# LB_BIT_o7_IRLED-v03_1_1.net
KiCad netlist of a schematic drawn in EAGLE
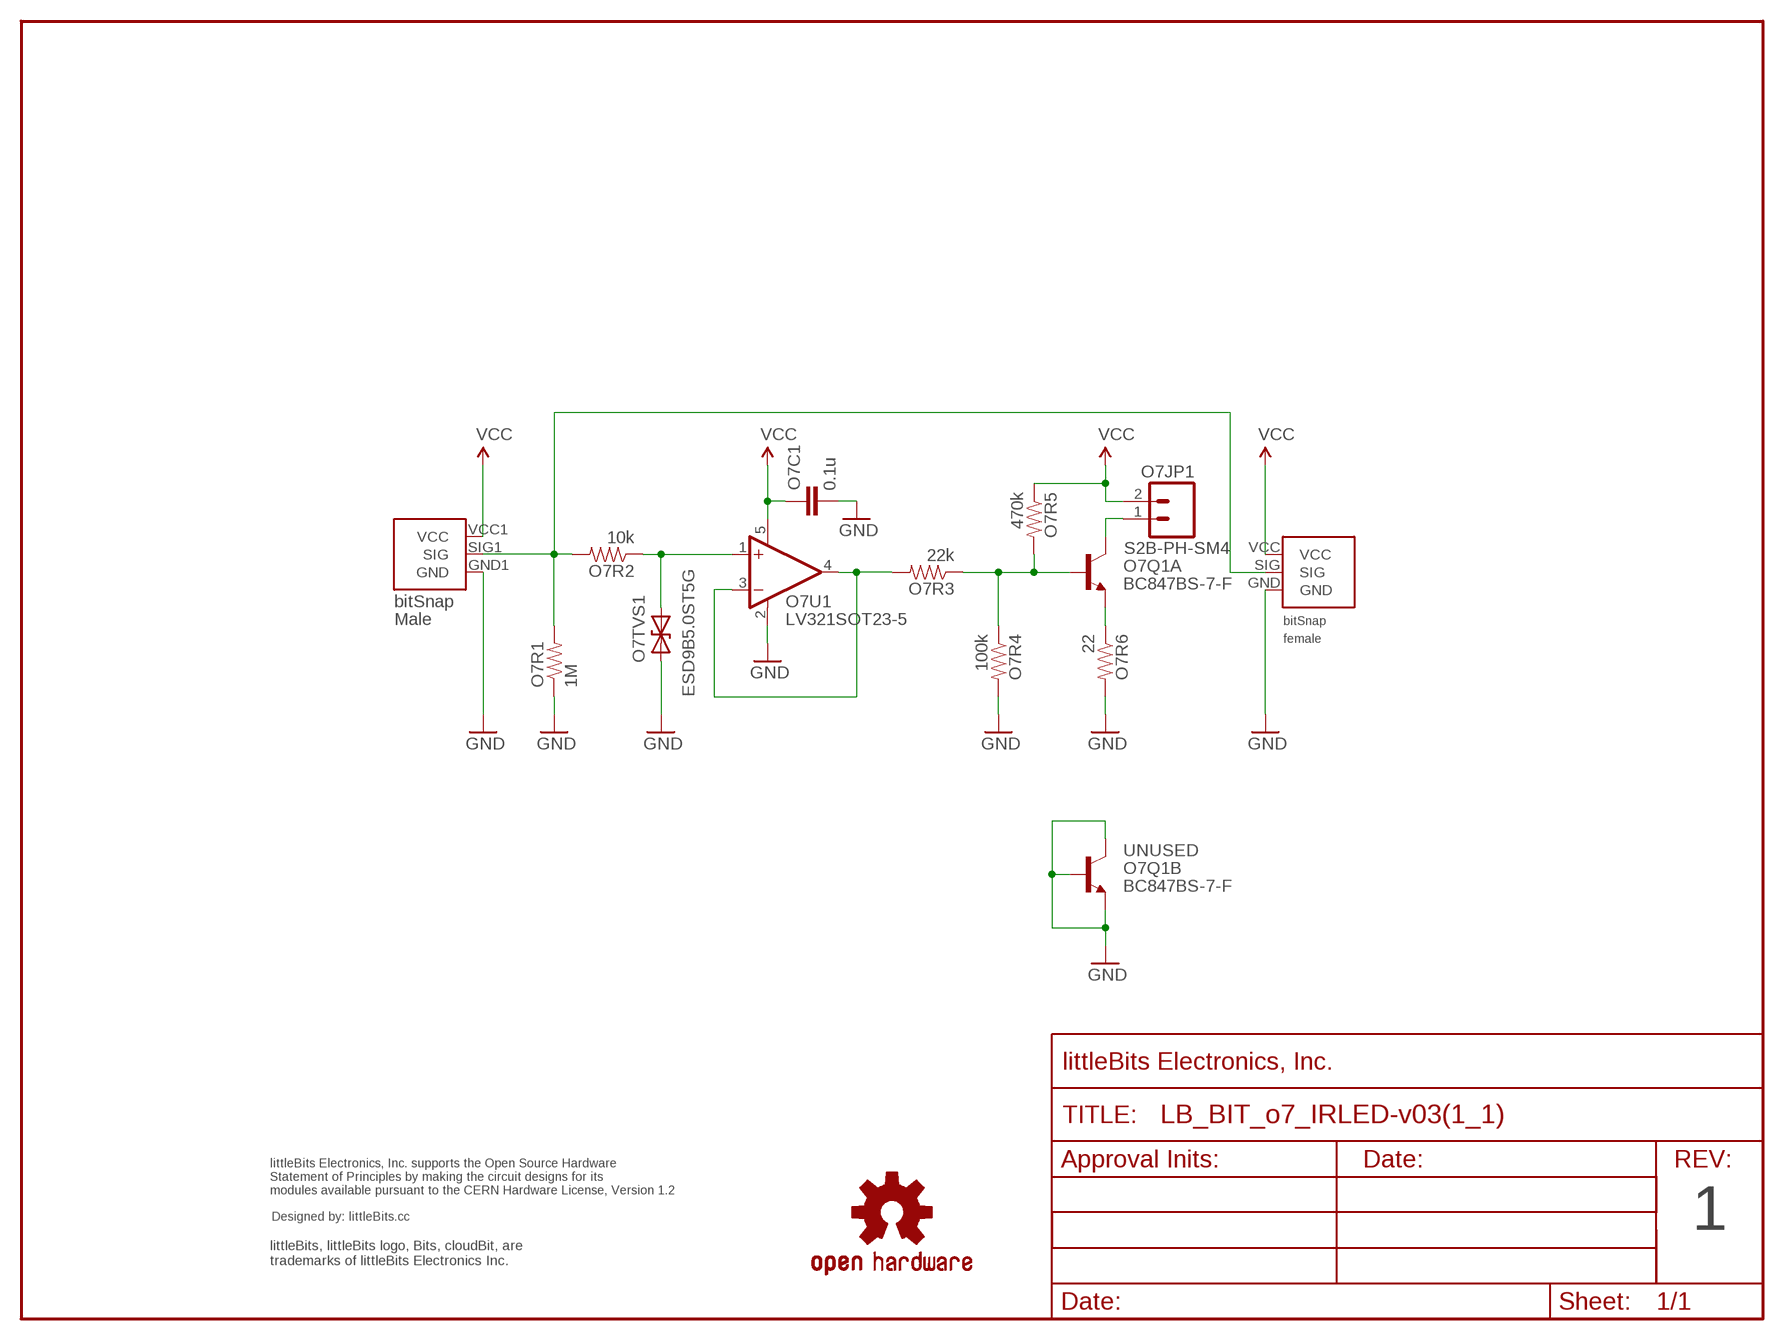
[diagram p0: schematic, sheet 1]

(export (version "E")
  (design (tool "Eeschema 10.0.6"))
  (components
    (comp (ref "O7BSF1")
      (value "BITSNAP_V03_FEMALE")
      (footprint "eagle-import:BITSNAP_V03_FEMALE")
      (libsource (lib "eagle-import") (part "BITSNAP_V03_FEMALE"))
    )
    (comp (ref "O7BSM1")
      (value "BITSNAP_V03_MALE")
      (footprint "eagle-import:BITSNAP_V03_MALE")
      (libsource (lib "eagle-import") (part "BITSNAP_V03_MALE"))
    )
    (comp (ref "O7C1")
      (value "0.1u")
      (footprint "eagle-import:CAP-0603")
      (libsource (lib "eagle-import") (part "CAPCAP-0603"))
    )
    (comp (ref "O7JP1")
      (value "S2B-PH-SM4")
      (footprint "eagle-import:S2B-PH")
      (libsource (lib "eagle-import") (part "M02-JST-2MM-SMT"))
    )
    (comp (ref "O7Q1")
      (value "BC847BS-7-F")
      (footprint "eagle-import:SOT-363_PHILLIPS")
      (libsource (lib "eagle-import") (part "TRANS-BJT_NPN-DUAL-BC847BS"))
    )
    (comp (ref "O7R1")
      (value "1M")
      (footprint "eagle-import:RES-0603")
      (libsource (lib "eagle-import") (part "RESISTOR0603"))
    )
    (comp (ref "O7R2")
      (value "10k")
      (footprint "eagle-import:RES-0603")
      (libsource (lib "eagle-import") (part "RESISTOR0603"))
    )
    (comp (ref "O7R3")
      (value "22k")
      (footprint "eagle-import:RES-0603")
      (libsource (lib "eagle-import") (part "RESISTOR0603"))
    )
    (comp (ref "O7R4")
      (value "100k")
      (footprint "eagle-import:RES-0603")
      (libsource (lib "eagle-import") (part "RESISTOR0603"))
    )
    (comp (ref "O7R5")
      (value "470k")
      (footprint "eagle-import:RES-0603")
      (libsource (lib "eagle-import") (part "RESISTOR0603"))
    )
    (comp (ref "O7R6")
      (value "22")
      (footprint "eagle-import:RES-0603")
      (libsource (lib "eagle-import") (part "RESISTOR0603"))
    )
    (comp (ref "O7TVS1")
      (value "ESD9B5.0ST5G")
      (footprint "eagle-import:SOD-923")
      (libsource (lib "eagle-import") (part "DIODE-TVSSOD-923"))
    )
    (comp (ref "O7U1")
      (value "LV321SOT23-5")
      (footprint "eagle-import:SOT23-5")
      (libsource (lib "eagle-import") (part "LV321SOT23-5"))
    )
    (comp (ref "U$5")
      (value "FRAME-LETTER-OHWOHW")
      (footprint "eagle-import:FABDWG01-OHW")
      (libsource (lib "eagle-import") (part "FRAME-LETTER-OHWOHW"))
    )
    (comp (ref "U$8")
      (value "OSHWCREDIT")
      (footprint "eagle-import:OSHWCREDIT")
      (libsource (lib "eagle-import") (part "OSHWCREDIT"))
    )
    (comp (ref "U$14")
      (value "OSHW-LOGOL")
      (footprint "eagle-import:OSHW-LOGO-L")
      (libsource (lib "eagle-import") (part "OSHW-LOGOL"))
    )
  )
  (nets
    (net (code "1") (name "GND") (class "Default")
      (node (ref "O7BSF1") (pin "GND") (pinfunction "GND_GND") (pintype "bidirectional"))
      (node (ref "O7BSM1") (pin "GND1") (pinfunction "GND_GND1") (pintype "bidirectional"))
      (node (ref "O7C1") (pin "2") (pinfunction "2_2") (pintype "passive"))
      (node (ref "O7Q1") (pin "3") (pinfunction "C_3") (pintype "passive"))
      (node (ref "O7Q1") (pin "4") (pinfunction "E_4") (pintype "passive"))
      (node (ref "O7Q1") (pin "5") (pinfunction "B_5") (pintype "passive"))
      (node (ref "O7R1") (pin "1") (pinfunction "1_1") (pintype "passive"))
      (node (ref "O7R4") (pin "2") (pinfunction "2_2") (pintype "passive"))
      (node (ref "O7R6") (pin "2") (pinfunction "2_2") (pintype "passive"))
      (node (ref "O7TVS1") (pin "1") (pinfunction "A_1") (pintype "passive"))
      (node (ref "O7U1") (pin "2") (pinfunction "V-_2") (pintype "power_in"))
    )
    (net (code "2") (name "Net-(O7BSM1-SIG)") (class "Default")
      (node (ref "O7BSF1") (pin "SIG") (pinfunction "SIG_SIG") (pintype "bidirectional"))
      (node (ref "O7BSM1") (pin "SIG1") (pinfunction "SIG_SIG1") (pintype "bidirectional"))
      (node (ref "O7R1") (pin "2") (pinfunction "2_2") (pintype "passive"))
      (node (ref "O7R2") (pin "2") (pinfunction "2_2") (pintype "passive"))
    )
    (net (code "3") (name "Net-(O7Q1A-B)") (class "Default")
      (node (ref "O7Q1") (pin "2") (pinfunction "B_2") (pintype "passive"))
      (node (ref "O7R3") (pin "1") (pinfunction "1_1") (pintype "passive"))
      (node (ref "O7R4") (pin "1") (pinfunction "1_1") (pintype "passive"))
      (node (ref "O7R5") (pin "2") (pinfunction "2_2") (pintype "passive"))
    )
    (net (code "4") (name "Net-(O7Q1A-C)") (class "Default")
      (node (ref "O7JP1") (pin "1") (pinfunction "1_1") (pintype "passive"))
      (node (ref "O7Q1") (pin "6") (pinfunction "C_6") (pintype "passive"))
    )
    (net (code "5") (name "Net-(O7Q1A-E)") (class "Default")
      (node (ref "O7Q1") (pin "1") (pinfunction "E_1") (pintype "passive"))
      (node (ref "O7R6") (pin "1") (pinfunction "1_1") (pintype "passive"))
    )
    (net (code "6") (name "Net-(O7TVS1-C)") (class "Default")
      (node (ref "O7R2") (pin "1") (pinfunction "1_1") (pintype "passive"))
      (node (ref "O7TVS1") (pin "2") (pinfunction "C_2") (pintype "passive"))
      (node (ref "O7U1") (pin "1") (pinfunction "+IN_1") (pintype "input"))
    )
    (net (code "7") (name "Net-(O7U1--IN)") (class "Default")
      (node (ref "O7R3") (pin "2") (pinfunction "2_2") (pintype "passive"))
      (node (ref "O7U1") (pin "3") (pinfunction "-IN_3") (pintype "input"))
      (node (ref "O7U1") (pin "4") (pinfunction "OUT_4") (pintype "output"))
    )
    (net (code "8") (name "VCC") (class "Default")
      (node (ref "O7BSF1") (pin "VCC") (pinfunction "VCC_VCC") (pintype "bidirectional"))
      (node (ref "O7BSM1") (pin "VCC1") (pinfunction "VCC_VCC1") (pintype "bidirectional"))
      (node (ref "O7C1") (pin "1") (pinfunction "1_1") (pintype "passive"))
      (node (ref "O7JP1") (pin "2") (pinfunction "2_2") (pintype "passive"))
      (node (ref "O7R5") (pin "1") (pinfunction "1_1") (pintype "passive"))
      (node (ref "O7U1") (pin "5") (pinfunction "V+_5") (pintype "power_in"))
    )
  )
)
